# sr_motors.net
KiCad netlist of a schematic drawn in EAGLE
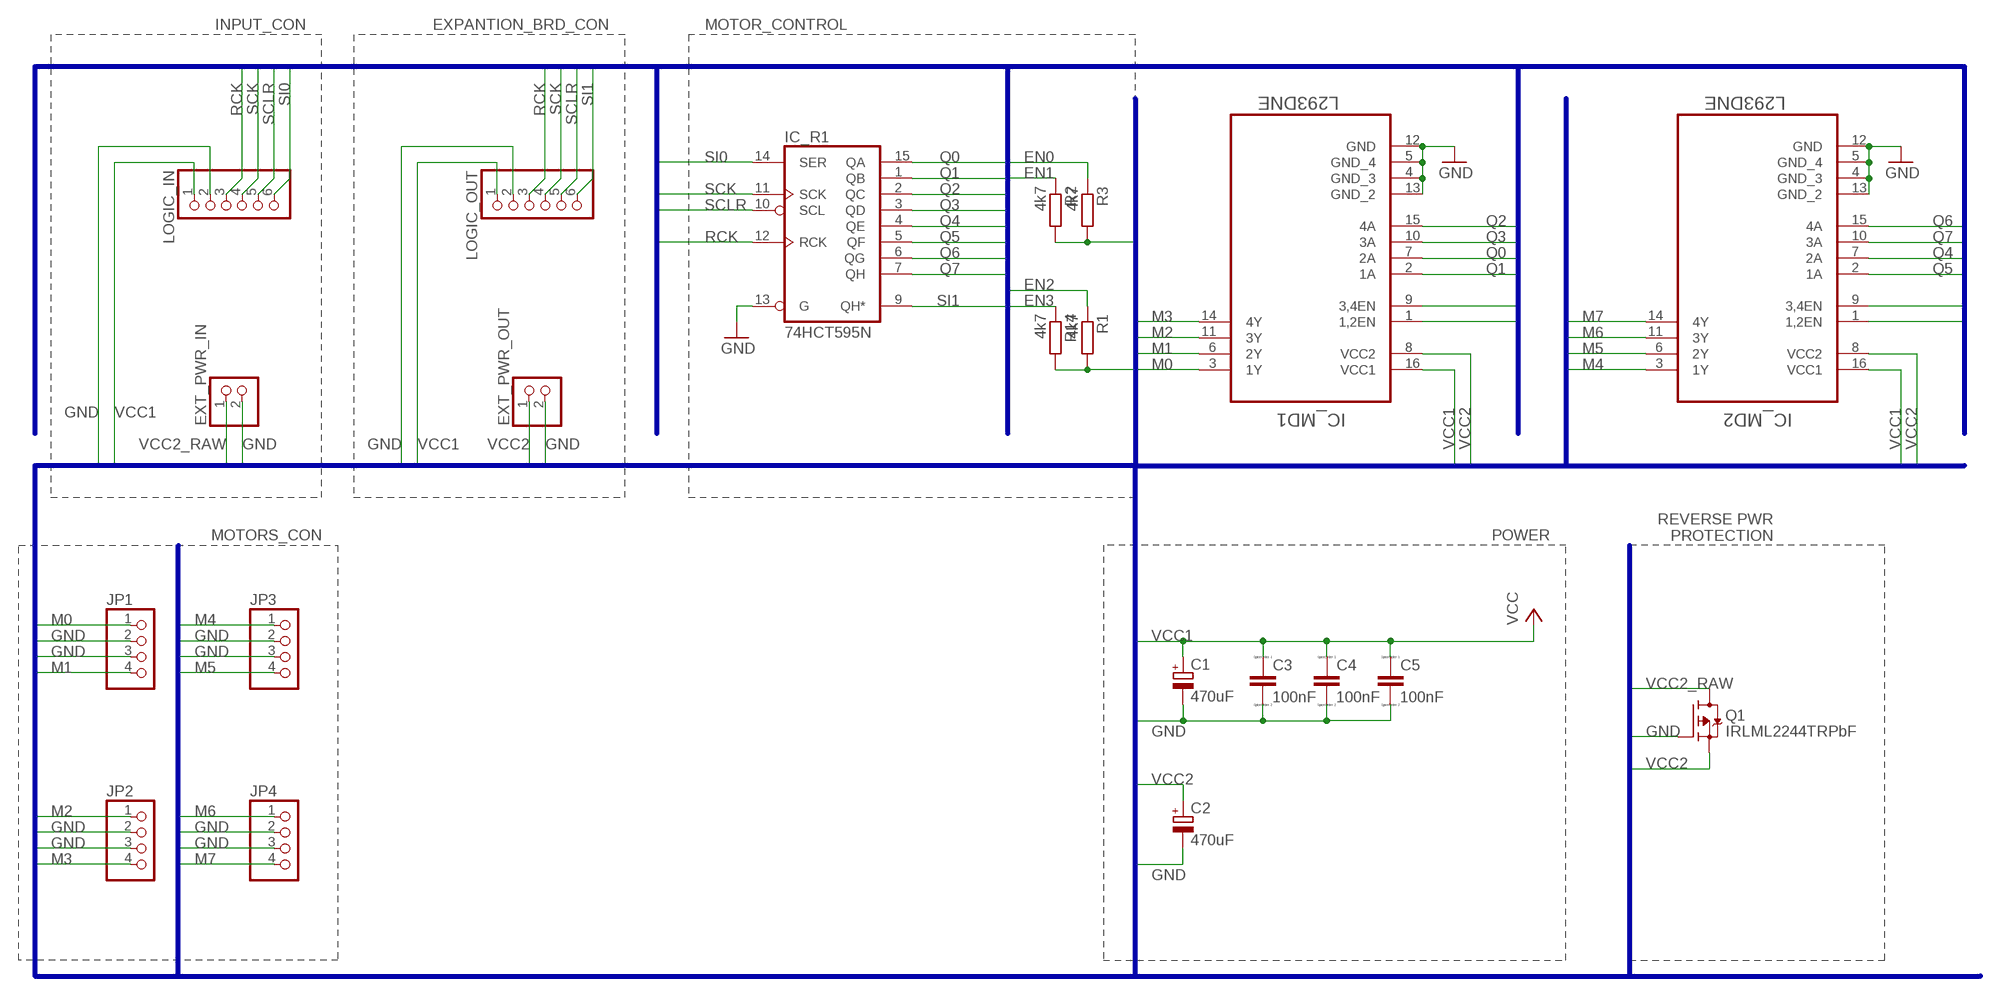
[diagram p0: schematic, sheet 1]

(export (version "E")
  (design (tool "Eeschema 10.0.6"))
  (components
    (comp (ref "C1")
      (value "470uF")
      (footprint "eagle-import:TT2D6")
      (libsource (lib "eagle-import") (part "CPOL-EUTT2D6"))
    )
    (comp (ref "C2")
      (value "470uF")
      (footprint "eagle-import:TT2D6")
      (libsource (lib "eagle-import") (part "CPOL-EUTT2D6"))
    )
    (comp (ref "C3")
      (value "100nF")
      (footprint "eagle-import:C0805")
      (libsource (lib "eagle-import") (part "C"))
    )
    (comp (ref "C4")
      (value "100nF")
      (footprint "eagle-import:C0805")
      (libsource (lib "eagle-import") (part "C"))
    )
    (comp (ref "C5")
      (value "100nF")
      (footprint "eagle-import:C0805")
      (libsource (lib "eagle-import") (part "C"))
    )
    (comp (ref "EXT_PWR_IN")
      (value "PINHD-1X2")
      (footprint "eagle-import:1X02")
      (libsource (lib "eagle-import") (part "PINHD-1X2"))
    )
    (comp (ref "EXT_PWR_OUT")
      (value "PINHD-1X2")
      (footprint "eagle-import:1X02")
      (libsource (lib "eagle-import") (part "PINHD-1X2"))
    )
    (comp (ref "IC_MD1")
      (value "L293DNE")
      (footprint "eagle-import:DIP254P762X508-16")
      (libsource (lib "eagle-import") (part "L293DNE"))
    )
    (comp (ref "IC_MD2")
      (value "L293DNE")
      (footprint "eagle-import:DIP254P762X508-16")
      (libsource (lib "eagle-import") (part "L293DNE"))
    )
    (comp (ref "IC_R1")
      (value "74HCT595N")
      (footprint "eagle-import:DIL16")
      (libsource (lib "eagle-import") (part "74595NHCT"))
    )
    (comp (ref "JP1")
      (value "PINHD-1X4")
      (footprint "eagle-import:1X04")
      (libsource (lib "eagle-import") (part "PINHD-1X4"))
    )
    (comp (ref "JP2")
      (value "PINHD-1X4")
      (footprint "eagle-import:1X04")
      (libsource (lib "eagle-import") (part "PINHD-1X4"))
    )
    (comp (ref "JP3")
      (value "PINHD-1X4")
      (footprint "eagle-import:1X04")
      (libsource (lib "eagle-import") (part "PINHD-1X4"))
    )
    (comp (ref "JP4")
      (value "PINHD-1X4")
      (footprint "eagle-import:1X04")
      (libsource (lib "eagle-import") (part "PINHD-1X4"))
    )
    (comp (ref "LOGIC_IN")
      (value "PINHD-1X6")
      (footprint "eagle-import:1X06")
      (libsource (lib "eagle-import") (part "PINHD-1X6"))
    )
    (comp (ref "LOGIC_OUT")
      (value "PINHD-1X6")
      (footprint "eagle-import:1X06")
      (libsource (lib "eagle-import") (part "PINHD-1X6"))
    )
    (comp (ref "Q1")
      (value "IRLML2244TRPbF")
      (footprint "eagle-import:SOT23")
      (libsource (lib "eagle-import") (part "MOSFET-P-SOT23"))
    )
    (comp (ref "R1")
      (value "4k7")
      (footprint "eagle-import:M0805")
      (libsource (lib "eagle-import") (part "R-EU_M0805"))
    )
    (comp (ref "R2")
      (value "4k7")
      (footprint "eagle-import:M0805")
      (libsource (lib "eagle-import") (part "R-EU_M0805"))
    )
    (comp (ref "R3")
      (value "4k7")
      (footprint "eagle-import:M0805")
      (libsource (lib "eagle-import") (part "R-EU_M0805"))
    )
    (comp (ref "R14")
      (value "4k7")
      (footprint "eagle-import:M0805")
      (libsource (lib "eagle-import") (part "R-EU_M0805"))
    )
  )
  (nets
    (net (code "1") (name "/EN0") (class "Default")
      (node (ref "IC_MD1") (pin "1") (pinfunction "1,2EN_1") (pintype "input"))
      (node (ref "R3") (pin "1") (pinfunction "1_1") (pintype "passive"))
    )
    (net (code "2") (name "/EN1") (class "Default")
      (node (ref "IC_MD1") (pin "9") (pinfunction "3,4EN_9") (pintype "input"))
      (node (ref "R2") (pin "1") (pinfunction "1_1") (pintype "passive"))
    )
    (net (code "3") (name "/EN2") (class "Default")
      (node (ref "IC_MD2") (pin "1") (pinfunction "1,2EN_1") (pintype "input"))
      (node (ref "R1") (pin "1") (pinfunction "1_1") (pintype "passive"))
    )
    (net (code "4") (name "/EN3") (class "Default")
      (node (ref "IC_MD2") (pin "9") (pinfunction "3,4EN_9") (pintype "input"))
      (node (ref "R14") (pin "1") (pinfunction "1_1") (pintype "passive"))
    )
    (net (code "5") (name "/M0") (class "Default")
      (node (ref "IC_MD1") (pin "3") (pinfunction "1Y_3") (pintype "output"))
      (node (ref "JP1") (pin "1") (pinfunction "1_1") (pintype "passive"))
    )
    (net (code "6") (name "/M1") (class "Default")
      (node (ref "IC_MD1") (pin "6") (pinfunction "2Y_6") (pintype "output"))
      (node (ref "JP1") (pin "4") (pinfunction "4_4") (pintype "passive"))
    )
    (net (code "7") (name "/M2") (class "Default")
      (node (ref "IC_MD1") (pin "11") (pinfunction "3Y_11") (pintype "output"))
      (node (ref "JP2") (pin "1") (pinfunction "1_1") (pintype "passive"))
    )
    (net (code "8") (name "/M3") (class "Default")
      (node (ref "IC_MD1") (pin "14") (pinfunction "4Y_14") (pintype "output"))
      (node (ref "JP2") (pin "4") (pinfunction "4_4") (pintype "passive"))
    )
    (net (code "9") (name "/M4") (class "Default")
      (node (ref "IC_MD2") (pin "3") (pinfunction "1Y_3") (pintype "output"))
      (node (ref "JP3") (pin "1") (pinfunction "1_1") (pintype "passive"))
    )
    (net (code "10") (name "/M5") (class "Default")
      (node (ref "IC_MD2") (pin "6") (pinfunction "2Y_6") (pintype "output"))
      (node (ref "JP3") (pin "4") (pinfunction "4_4") (pintype "passive"))
    )
    (net (code "11") (name "/M6") (class "Default")
      (node (ref "IC_MD2") (pin "11") (pinfunction "3Y_11") (pintype "output"))
      (node (ref "JP4") (pin "1") (pinfunction "1_1") (pintype "passive"))
    )
    (net (code "12") (name "/M7") (class "Default")
      (node (ref "IC_MD2") (pin "14") (pinfunction "4Y_14") (pintype "output"))
      (node (ref "JP4") (pin "4") (pinfunction "4_4") (pintype "passive"))
    )
    (net (code "13") (name "/Q0") (class "Default")
      (node (ref "IC_MD1") (pin "7") (pinfunction "2A_7") (pintype "input"))
      (node (ref "IC_R1") (pin "15") (pinfunction "QA_15") (pintype "tri_state"))
    )
    (net (code "14") (name "/Q1") (class "Default")
      (node (ref "IC_MD1") (pin "2") (pinfunction "1A_2") (pintype "input"))
      (node (ref "IC_R1") (pin "1") (pinfunction "QB_1") (pintype "tri_state"))
    )
    (net (code "15") (name "/Q2") (class "Default")
      (node (ref "IC_MD1") (pin "15") (pinfunction "4A_15") (pintype "input"))
      (node (ref "IC_R1") (pin "2") (pinfunction "QC_2") (pintype "tri_state"))
    )
    (net (code "16") (name "/Q3") (class "Default")
      (node (ref "IC_MD1") (pin "10") (pinfunction "3A_10") (pintype "input"))
      (node (ref "IC_R1") (pin "3") (pinfunction "QD_3") (pintype "tri_state"))
    )
    (net (code "17") (name "/Q4") (class "Default")
      (node (ref "IC_MD2") (pin "7") (pinfunction "2A_7") (pintype "input"))
      (node (ref "IC_R1") (pin "4") (pinfunction "QE_4") (pintype "tri_state"))
    )
    (net (code "18") (name "/Q5") (class "Default")
      (node (ref "IC_MD2") (pin "2") (pinfunction "1A_2") (pintype "input"))
      (node (ref "IC_R1") (pin "5") (pinfunction "QF_5") (pintype "tri_state"))
    )
    (net (code "19") (name "/Q6") (class "Default")
      (node (ref "IC_MD2") (pin "15") (pinfunction "4A_15") (pintype "input"))
      (node (ref "IC_R1") (pin "6") (pinfunction "QG_6") (pintype "tri_state"))
    )
    (net (code "20") (name "/Q7") (class "Default")
      (node (ref "IC_MD2") (pin "10") (pinfunction "3A_10") (pintype "input"))
      (node (ref "IC_R1") (pin "7") (pinfunction "QH_7") (pintype "tri_state"))
    )
    (net (code "21") (name "/RCK") (class "Default")
      (node (ref "IC_R1") (pin "12") (pinfunction "RCK_12") (pintype "input"))
      (node (ref "LOGIC_IN") (pin "3") (pinfunction "3_3") (pintype "passive"))
      (node (ref "LOGIC_OUT") (pin "3") (pinfunction "3_3") (pintype "passive"))
    )
    (net (code "22") (name "/SCK") (class "Default")
      (node (ref "IC_R1") (pin "11") (pinfunction "SCK_11") (pintype "input"))
      (node (ref "LOGIC_IN") (pin "4") (pinfunction "4_4") (pintype "passive"))
      (node (ref "LOGIC_OUT") (pin "4") (pinfunction "4_4") (pintype "passive"))
    )
    (net (code "23") (name "/SCLR") (class "Default")
      (node (ref "IC_R1") (pin "10") (pinfunction "SCL_10") (pintype "input"))
      (node (ref "LOGIC_IN") (pin "5") (pinfunction "5_5") (pintype "passive"))
      (node (ref "LOGIC_OUT") (pin "5") (pinfunction "5_5") (pintype "passive"))
    )
    (net (code "24") (name "/SI0") (class "Default")
      (node (ref "IC_R1") (pin "14") (pinfunction "SER_14") (pintype "input"))
      (node (ref "LOGIC_IN") (pin "6") (pinfunction "6_6") (pintype "passive"))
    )
    (net (code "25") (name "/SI1") (class "Default")
      (node (ref "IC_R1") (pin "9") (pinfunction "QH*_9") (pintype "tri_state"))
      (node (ref "LOGIC_OUT") (pin "6") (pinfunction "6_6") (pintype "passive"))
    )
    (net (code "26") (name "/VCC2") (class "Default")
      (node (ref "C2") (pin "+") (pinfunction "+_+") (pintype "passive"))
      (node (ref "EXT_PWR_OUT") (pin "1") (pinfunction "1_1") (pintype "passive"))
      (node (ref "IC_MD1") (pin "8") (pinfunction "VCC2_8") (pintype "power_in"))
      (node (ref "IC_MD2") (pin "8") (pinfunction "VCC2_8") (pintype "power_in"))
      (node (ref "Q1") (pin "2") (pinfunction "S_2") (pintype "passive"))
    )
    (net (code "27") (name "/VCC2_RAW") (class "Default")
      (node (ref "EXT_PWR_IN") (pin "1") (pinfunction "1_1") (pintype "passive"))
      (node (ref "Q1") (pin "3") (pinfunction "D_3") (pintype "passive"))
    )
    (net (code "29") (name "GND") (class "Default")
      (node (ref "C1") (pin "-") (pinfunction "-_-") (pintype "passive"))
      (node (ref "C2") (pin "-") (pinfunction "-_-") (pintype "passive"))
      (node (ref "C3") (pin "2") (pinfunction "2_2") (pintype "passive"))
      (node (ref "C4") (pin "2") (pinfunction "2_2") (pintype "passive"))
      (node (ref "C5") (pin "2") (pinfunction "2_2") (pintype "passive"))
      (node (ref "EXT_PWR_IN") (pin "2") (pinfunction "2_2") (pintype "passive"))
      (node (ref "EXT_PWR_OUT") (pin "2") (pinfunction "2_2") (pintype "passive"))
      (node (ref "IC_MD1") (pin "12") (pinfunction "GND_12") (pintype "passive"))
      (node (ref "IC_MD1") (pin "13") (pinfunction "GND_2_13") (pintype "passive"))
      (node (ref "IC_MD1") (pin "4") (pinfunction "GND_3_4") (pintype "passive"))
      (node (ref "IC_MD1") (pin "5") (pinfunction "GND_4_5") (pintype "passive"))
      (node (ref "IC_MD2") (pin "12") (pinfunction "GND_12") (pintype "passive"))
      (node (ref "IC_MD2") (pin "13") (pinfunction "GND_2_13") (pintype "passive"))
      (node (ref "IC_MD2") (pin "4") (pinfunction "GND_3_4") (pintype "passive"))
      (node (ref "IC_MD2") (pin "5") (pinfunction "GND_4_5") (pintype "passive"))
      (node (ref "IC_R1") (pin "13") (pinfunction "G_13") (pintype "input"))
      (node (ref "JP1") (pin "2") (pinfunction "2_2") (pintype "passive"))
      (node (ref "JP1") (pin "3") (pinfunction "3_3") (pintype "passive"))
      (node (ref "JP2") (pin "2") (pinfunction "2_2") (pintype "passive"))
      (node (ref "JP2") (pin "3") (pinfunction "3_3") (pintype "passive"))
      (node (ref "JP3") (pin "2") (pinfunction "2_2") (pintype "passive"))
      (node (ref "JP3") (pin "3") (pinfunction "3_3") (pintype "passive"))
      (node (ref "JP4") (pin "2") (pinfunction "2_2") (pintype "passive"))
      (node (ref "JP4") (pin "3") (pinfunction "3_3") (pintype "passive"))
      (node (ref "LOGIC_IN") (pin "2") (pinfunction "2_2") (pintype "passive"))
      (node (ref "LOGIC_OUT") (pin "2") (pinfunction "2_2") (pintype "passive"))
      (node (ref "Q1") (pin "1") (pinfunction "G_1") (pintype "passive"))
    )
    (net (code "30") (name "VCC") (class "Default")
      (node (ref "C1") (pin "+") (pinfunction "+_+") (pintype "passive"))
      (node (ref "C3") (pin "1") (pinfunction "1_1") (pintype "passive"))
      (node (ref "C4") (pin "1") (pinfunction "1_1") (pintype "passive"))
      (node (ref "C5") (pin "1") (pinfunction "1_1") (pintype "passive"))
      (node (ref "IC_MD1") (pin "16") (pinfunction "VCC1_16") (pintype "power_in"))
      (node (ref "IC_MD2") (pin "16") (pinfunction "VCC1_16") (pintype "power_in"))
      (node (ref "LOGIC_IN") (pin "1") (pinfunction "1_1") (pintype "passive"))
      (node (ref "LOGIC_OUT") (pin "1") (pinfunction "1_1") (pintype "passive"))
      (node (ref "R1") (pin "2") (pinfunction "2_2") (pintype "passive"))
      (node (ref "R14") (pin "2") (pinfunction "2_2") (pintype "passive"))
      (node (ref "R2") (pin "2") (pinfunction "2_2") (pintype "passive"))
      (node (ref "R3") (pin "2") (pinfunction "2_2") (pintype "passive"))
    )
  )
)
